# BroadNode.net
KiCad netlist of a schematic drawn in EasyEDA
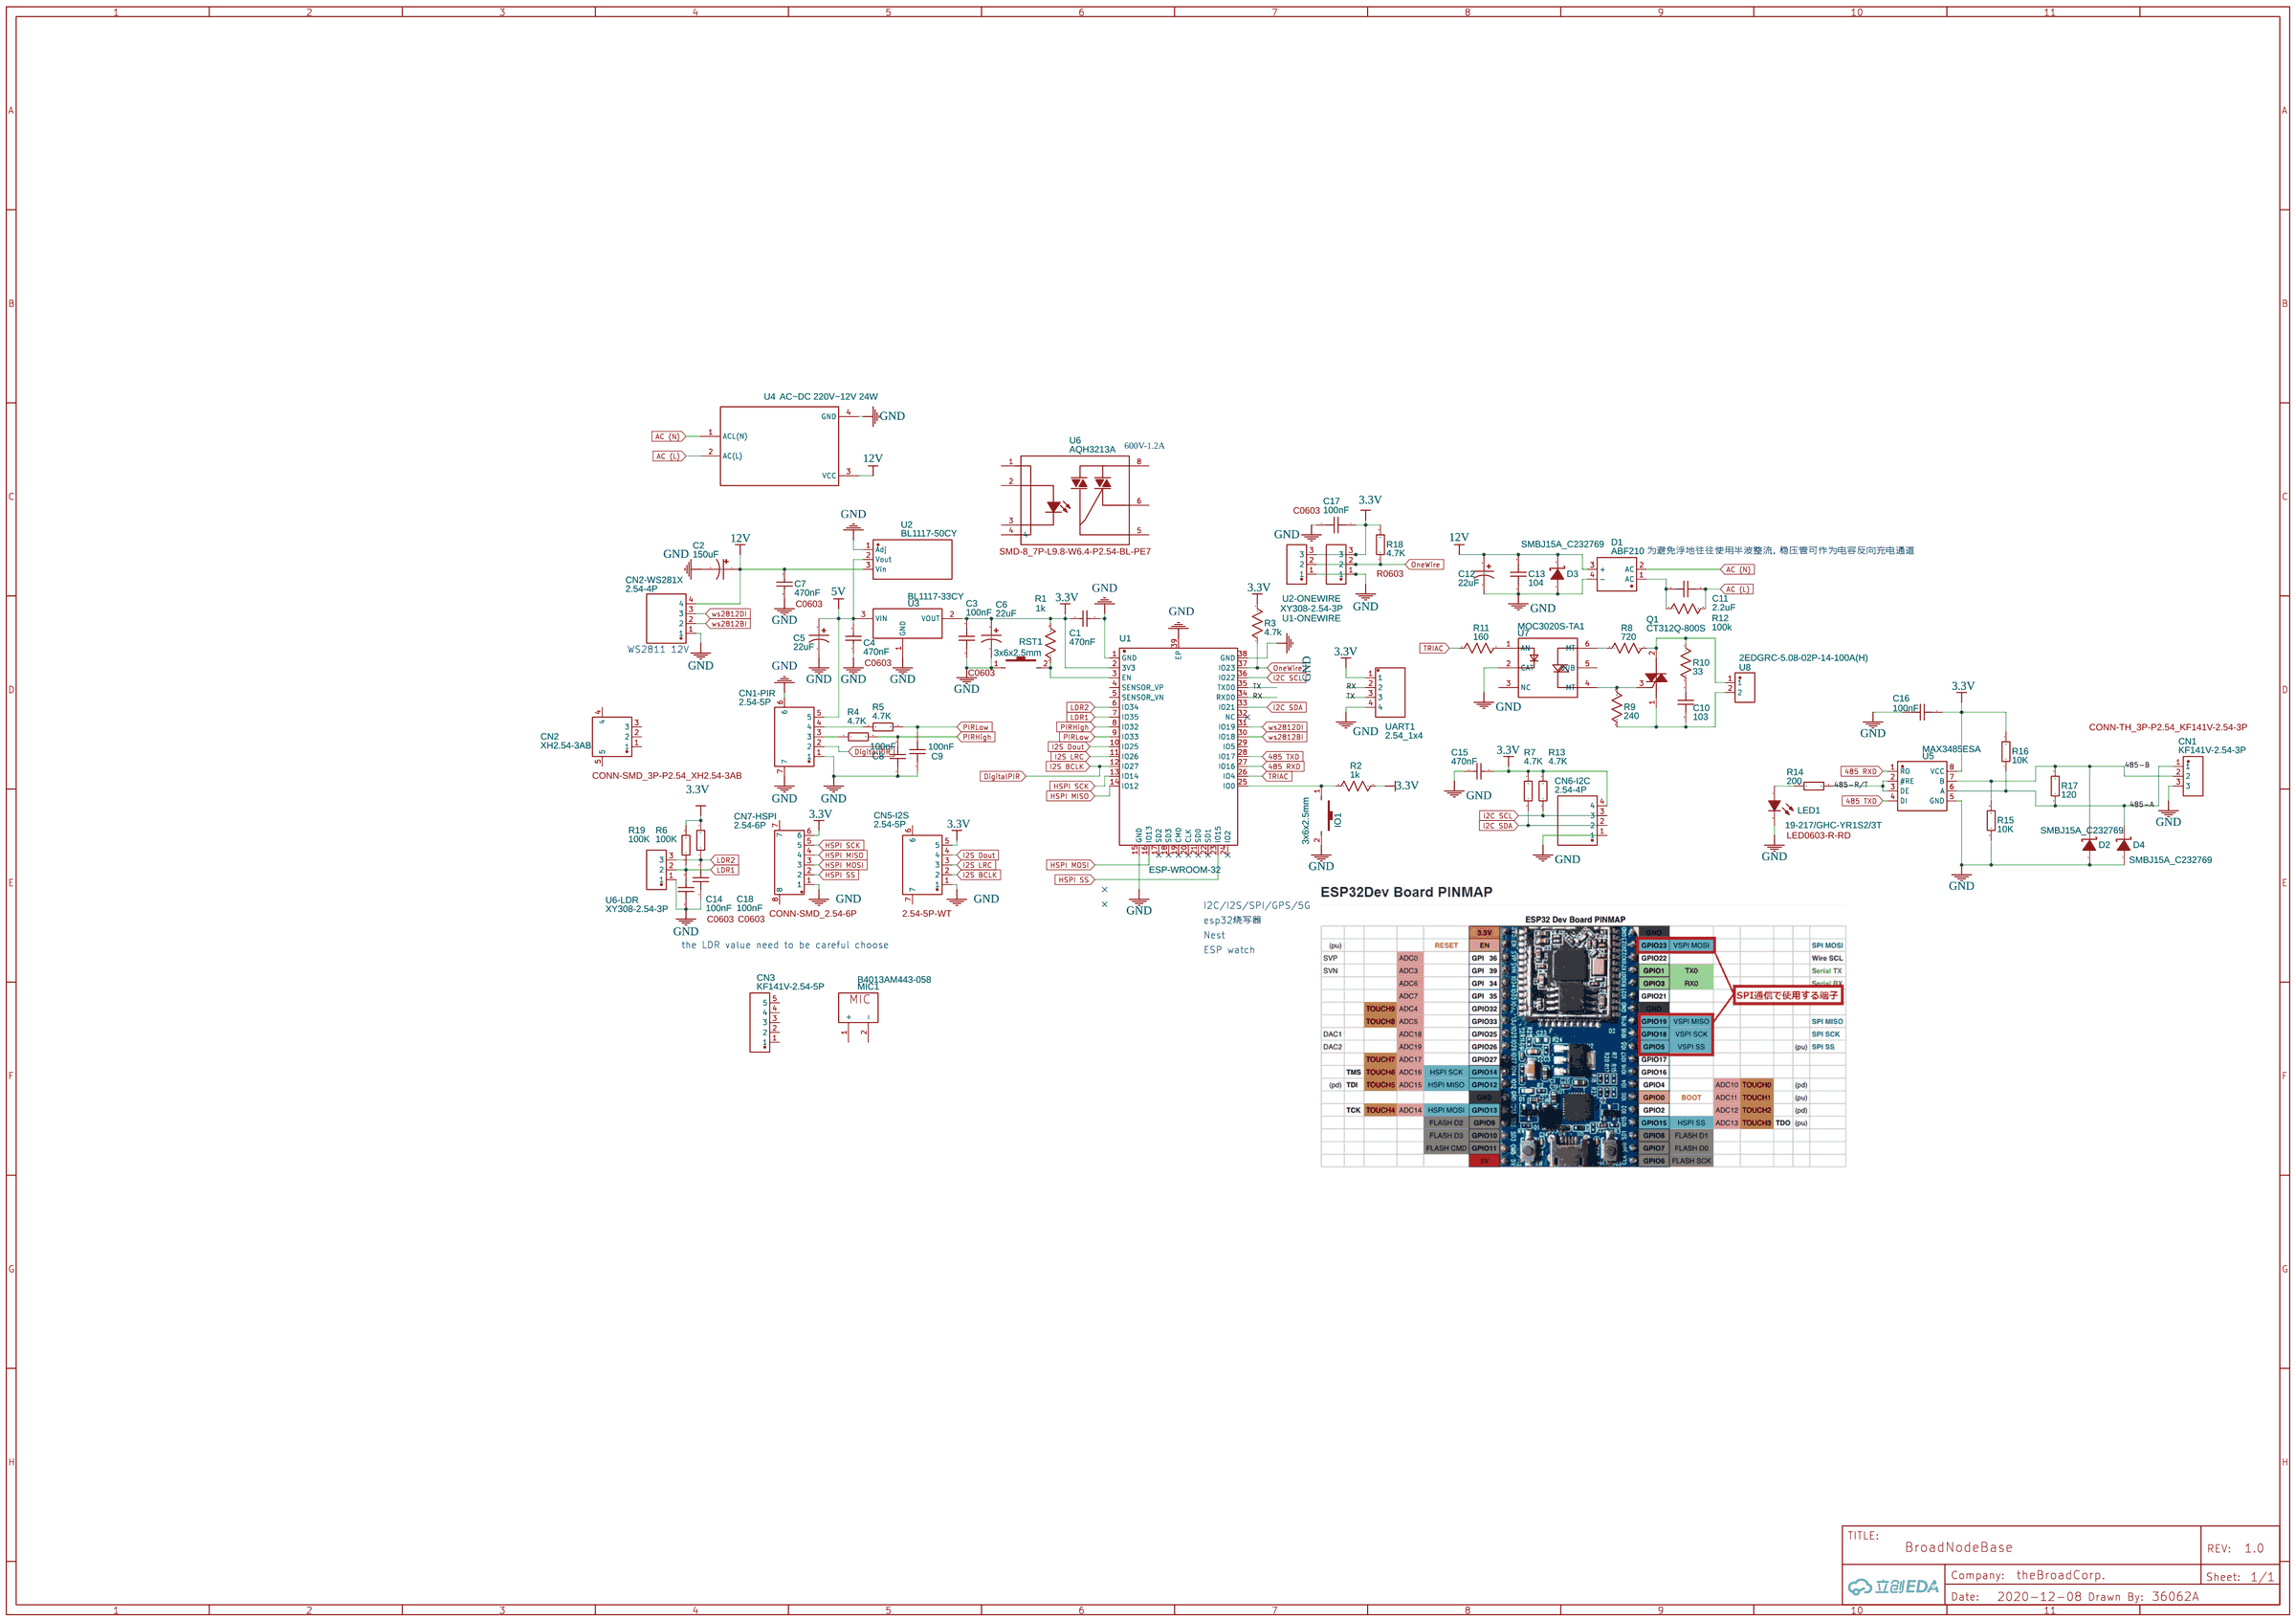
[diagram p0: schematic sheet]

(export (version "E")
  (design (tool "Eeschema 10.0.6"))
  (components
    (comp (ref "C1")
      (value "470nF")
      (fields
        (field (name "BOM_Manufacturer Part") "CL10B474KA8NNNC")
        (field (name "BOM_Supplier Part") "C1623")
      )
      (libsource (lib "") (part "CL10B474KA8NNNC"))
    )
    (comp (ref "C2")
      (value "150uF")
      (fields
        (field (name "BOM_Manufacturer Part") "OVZ151M1C0807-TRO")
        (field (name "BOM_Supplier Part") "C250092")
      )
      (libsource (lib "") (part "OVZ151M1C0807-TRO"))
    )
    (comp (ref "C3")
      (value "100nF")
      (fields
        (field (name "BOM_Manufacturer Part") "CC0603KRX7R9BB104")
        (field (name "BOM_Supplier Part") "C14663")
      )
      (libsource (lib "") (part "CC0603KRX7R9BB104_3"))
    )
    (comp (ref "C4")
      (value "470nF")
      (fields
        (field (name "BOM_Manufacturer Part") "CL10B474KA8NNNC")
        (field (name "BOM_Supplier Part") "C1623")
      )
      (libsource (lib "") (part "CL10B474KA8NNNC_2"))
    )
    (comp (ref "C5")
      (value "22uF")
      (fields
        (field (name "BOM_Manufacturer Part") "OCV220M1VTR-0606")
        (field (name "BOM_Supplier Part") "C473426")
      )
      (libsource (lib "") (part "OCV220M1VTR-0606"))
    )
    (comp (ref "C6")
      (value "22uF")
      (fields
        (field (name "BOM_Manufacturer Part") "OCV220M1VTR-0606")
        (field (name "BOM_Supplier Part") "C473426")
      )
      (libsource (lib "") (part "OCV220M1VTR-0606"))
    )
    (comp (ref "C7")
      (value "470nF")
      (fields
        (field (name "BOM_Manufacturer Part") "CL10B474KA8NNNC")
        (field (name "BOM_Supplier Part") "C1623")
      )
      (libsource (lib "") (part "CL10B474KA8NNNC_1"))
    )
    (comp (ref "C8")
      (value "100nF")
      (fields
        (field (name "BOM_Manufacturer Part") "CC0603KRX7R9BB104")
        (field (name "BOM_Supplier Part") "C14663")
      )
      (libsource (lib "") (part "CC0603KRX7R9BB104_1"))
    )
    (comp (ref "C9")
      (value "100nF")
      (fields
        (field (name "BOM_Manufacturer Part") "CC0603KRX7R9BB104")
        (field (name "BOM_Supplier Part") "C14663")
      )
      (libsource (lib "") (part "CC0603KRX7R9BB104_1"))
    )
    (comp (ref "C10") (value "103") (libsource (lib "") (part "Cap_0603_US_1")))
    (comp (ref "C11") (value "2.2uF") (libsource (lib "") (part "Cap_0603_US")))
    (comp (ref "C12")
      (value "22uF")
      (fields
        (field (name "BOM_Manufacturer Part") "OCV220M1VTR-0606")
        (field (name "BOM_Supplier Part") "C473426")
      )
      (libsource (lib "") (part "OCV220M1VTR-0606_1"))
    )
    (comp (ref "C13") (value "104") (libsource (lib "") (part "Cap_0603_US_1")))
    (comp (ref "C14")
      (value "100nF")
      (fields
        (field (name "BOM_Manufacturer Part") "CC0603KRX7R9BB104")
        (field (name "BOM_Supplier Part") "C14663")
      )
      (libsource (lib "") (part "CC0603KRX7R9BB104"))
    )
    (comp (ref "C15")
      (value "470nF")
      (fields
        (field (name "BOM_Manufacturer Part") "CL10B474KA8NNNC")
        (field (name "BOM_Supplier Part") "C1623")
      )
      (libsource (lib "") (part "CL10B474KA8NNNC"))
    )
    (comp (ref "C16")
      (value "100nF")
      (fields
        (field (name "BOM_Manufacturer Part") "CC0603KRX7R9BB104")
        (field (name "BOM_Supplier Part") "C14663")
      )
      (libsource (lib "") (part "CC0603KRX7R9BB104_4"))
    )
    (comp (ref "C17")
      (value "100nF")
      (fields
        (field (name "BOM_Manufacturer Part") "CC0603KRX7R9BB104")
        (field (name "BOM_Supplier Part") "C14663")
      )
      (libsource (lib "") (part "CC0603KRX7R9BB104_5"))
    )
    (comp (ref "C18")
      (value "100nF")
      (fields
        (field (name "BOM_Manufacturer Part") "CC0603KRX7R9BB104")
        (field (name "BOM_Supplier Part") "C14663")
      )
      (libsource (lib "") (part "CC0603KRX7R9BB104_2"))
    )
    (comp (ref "CN1")
      (value "KF141V-2.54-3P")
      (fields (field (name "BOM_Supplier Part") "C475115"))
      (libsource (lib "") (part "KF141V-2.54-3P"))
    )
    (comp (ref "CN1-PIR")
      (value "2.54-5P")
      (fields (field (name "BOM_Supplier Part") "C146121"))
      (libsource (lib "") (part "2.54-5P_1"))
    )
    (comp (ref "CN2")
      (value "XH2.54-3AB")
      (fields (field (name "BOM_Supplier Part") "C146126"))
      (libsource (lib "") (part "XH2.54-3AB"))
    )
    (comp (ref "CN2-WS281X")
      (value "2.54-4P")
      (fields (field (name "BOM_Supplier Part") "C146120"))
      (libsource (lib "") (part "2.54-4P_1"))
    )
    (comp (ref "CN3")
      (value "KF141V-2.54-5P")
      (fields (field (name "BOM_Supplier Part") "C475117"))
      (libsource (lib "") (part "KF141V-2.54-5P"))
    )
    (comp (ref "CN5-I2S")
      (value "2.54-5P")
      (fields (field (name "BOM_Supplier Part") "C146121"))
      (libsource (lib "") (part "2.54-5P"))
    )
    (comp (ref "CN6-I2C")
      (value "2.54-4P")
      (fields (field (name "BOM_Supplier Part") "C146120"))
      (libsource (lib "") (part "2.54-4P"))
    )
    (comp (ref "CN7-HSPI")
      (value "2.54-6P")
      (fields (field (name "BOM_Supplier Part") "C146122"))
      (libsource (lib "") (part "2.54-6P"))
    )
    (comp (ref "D1")
      (value "ABF210")
      (fields (field (name "BOM_Supplier Part") "C169534"))
      (libsource (lib "") (part "ABF210"))
    )
    (comp (ref "D2")
      (value "SMBJ15A_C232769")
      (fields (field (name "BOM_Manufacturer Part") "SMBJ15A") (field (name "BOM_Supplier Part") "C232769"))
      (libsource (lib "") (part "Unknown_2115_45"))
    )
    (comp (ref "D3")
      (value "SMBJ15A_C232769")
      (fields (field (name "BOM_Manufacturer Part") "SMBJ15A") (field (name "BOM_Supplier Part") "C232769"))
      (libsource (lib "") (part "Unknown_1575_-230"))
    )
    (comp (ref "D4")
      (value "SMBJ15A_C232769")
      (fields (field (name "BOM_Manufacturer Part") "SMBJ15A") (field (name "BOM_Supplier Part") "C232769"))
      (libsource (lib "") (part "Unknown_2150_45"))
    )
    (comp (ref "IO1")
      (value "3x6x2.5mm")
      (fields (field (name "BOM_Supplier Part") "C5382"))
      (libsource (lib "") (part "Unknown_1340_15"))
    )
    (comp (ref "LED1")
      (value "19-217/GHC-YR1S2/3T")
      (fields (field (name "BOM_Supplier Part") "C72043"))
      (libsource (lib "") (part "19-217/GHC-YR1S2/3T"))
    )
    (comp (ref "MIC1")
      (value "B4013AM443-058")
      (fields (field (name "BOM_Supplier Part") "C233795"))
      (libsource (lib "") (part "B4013AM443-058"))
    )
    (comp (ref "Q1")
      (value "CT312Q-800S")
      (fields (field (name "BOM_Supplier Part") "C527795"))
      (libsource (lib "") (part "CT312Q-800S"))
    )
    (comp (ref "R1") (value "1k") (libsource (lib "") (part "Res_0603(1/10W)_US")))
    (comp (ref "R2") (value "1k") (libsource (lib "") (part "Res_0603(1/10W)_US_1")))
    (comp (ref "R3") (value "4.7k") (libsource (lib "") (part "Res_0603(1/10W)_US")))
    (comp (ref "R4")
      (value "4.7K")
      (fields
        (field (name "BOM_Manufacturer Part") "0603WAF4701T5E")
        (field (name "BOM_Supplier Part") "C23162")
      )
      (libsource (lib "") (part "0603WAF4701T5E"))
    )
    (comp (ref "R5")
      (value "4.7K")
      (fields
        (field (name "BOM_Manufacturer Part") "0603WAF4701T5E")
        (field (name "BOM_Supplier Part") "C23162")
      )
      (libsource (lib "") (part "0603WAF4701T5E"))
    )
    (comp (ref "R6")
      (value "100K")
      (fields
        (field (name "BOM_Manufacturer Part") "0603WAF1003T5E")
        (field (name "BOM_Supplier Part") "C25803")
      )
      (libsource (lib "") (part "0603WAF1003T5E"))
    )
    (comp (ref "R7")
      (value "4.7K")
      (fields
        (field (name "BOM_Manufacturer Part") "0603WAF4701T5E")
        (field (name "BOM_Supplier Part") "C23162")
      )
      (libsource (lib "") (part "0603WAF4701T5E_2"))
    )
    (comp (ref "R8") (value "720") (libsource (lib "") (part "Res_0603(1/10W)_US_3")))
    (comp (ref "R9") (value "240") (libsource (lib "") (part "Res_0603(1/10W)_US")))
    (comp (ref "R10") (value "33") (libsource (lib "") (part "Res_0603(1/10W)_US_2")))
    (comp (ref "R11") (value "160") (libsource (lib "") (part "Res_0603(1/10W)_US_3")))
    (comp (ref "R12") (value "100k") (libsource (lib "") (part "Res_0603(1/10W)_US_1")))
    (comp (ref "R13")
      (value "4.7K")
      (fields
        (field (name "BOM_Manufacturer Part") "0603WAF4701T5E")
        (field (name "BOM_Supplier Part") "C23162")
      )
      (libsource (lib "") (part "0603WAF4701T5E_2"))
    )
    (comp (ref "R14")
      (value "200")
      (fields
        (field (name "BOM_Manufacturer Part") "MCR03EZPJ201")
        (field (name "BOM_Supplier Part") "C253407")
      )
      (libsource (lib "") (part "MCR03EZPJ201"))
    )
    (comp (ref "R15")
      (value "10K")
      (fields
        (field (name "BOM_Manufacturer Part") "RMCF0603JT10K0")
        (field (name "BOM_Supplier Part") "C238881")
      )
      (libsource (lib "") (part "RMCF0603JT10K0"))
    )
    (comp (ref "R16")
      (value "10K")
      (fields
        (field (name "BOM_Manufacturer Part") "RMCF0603JT10K0")
        (field (name "BOM_Supplier Part") "C238881")
      )
      (libsource (lib "") (part "RMCF0603JT10K0"))
    )
    (comp (ref "R17")
      (value "120")
      (fields
        (field (name "BOM_Manufacturer Part") "MCR03EZPFX1200")
        (field (name "BOM_Supplier Part") "C253379")
      )
      (libsource (lib "") (part "MCR03EZPFX1200"))
    )
    (comp (ref "R18")
      (value "4.7K")
      (fields
        (field (name "BOM_Manufacturer Part") "0603WAF4701T5E")
        (field (name "BOM_Supplier Part") "C23162")
      )
      (libsource (lib "") (part "0603WAF4701T5E_1"))
    )
    (comp (ref "R19")
      (value "100K")
      (fields
        (field (name "BOM_Manufacturer Part") "0603WAF1003T5E")
        (field (name "BOM_Supplier Part") "C25803")
      )
      (libsource (lib "") (part "0603WAF1003T5E"))
    )
    (comp (ref "RST1")
      (value "3x6x2.5mm")
      (fields (field (name "BOM_Supplier Part") "C5382"))
      (libsource (lib "") (part "Unknown_1030_-140"))
    )
    (comp (ref "U1")
      (value "ESP-WROOM-32")
      (fields (field (name "BOM_Supplier Part") "C95209"))
      (libsource (lib "") (part "Unknown_1190_-50"))
    )
    (comp (ref "U1-ONEWIRE")
      (value "XY308-2.54-3P")
      (fields (field (name "BOM_Supplier Part") "C557686"))
      (libsource (lib "") (part "XY308-2.54-3P_1"))
    )
    (comp (ref "U2")
      (value "BL1117-50CY")
      (fields (field (name "BOM_Supplier Part") "C194636"))
      (libsource (lib "") (part "BL1117-50CY"))
    )
    (comp (ref "U2-ONEWIRE")
      (value "XY308-2.54-3P")
      (fields (field (name "BOM_Supplier Part") "C557686"))
      (libsource (lib "") (part "XY308-2.54-3P_2"))
    )
    (comp (ref "U3")
      (value "BL1117-33CY")
      (fields (field (name "BOM_Supplier Part") "C165080"))
      (libsource (lib "") (part "BL1117-33CY"))
    )
    (comp (ref "U4")
      (value "AC~DC 220V~12V 24W")
      (fields (field (name "BOM_Manufacturer Part") "New SchematicLib"))
      (libsource (lib "") (part "AC&#126;DC 220V&#126;12V 24W"))
    )
    (comp (ref "U5")
      (value "MAX3485ESA")
      (fields (field (name "BOM_Supplier Part") "C668204"))
      (libsource (lib "") (part "MAX3485ESA"))
    )
    (comp (ref "U6")
      (value "AQH3213A")
      (fields (field (name "BOM_Supplier Part") "C91557"))
      (libsource (lib "") (part "AQH3213A"))
    )
    (comp (ref "U6-LDR")
      (value "XY308-2.54-3P")
      (fields (field (name "BOM_Supplier Part") "C557686"))
      (libsource (lib "") (part "XY308-2.54-3P"))
    )
    (comp (ref "U7")
      (value "MOC3020S-TA1")
      (fields (field (name "BOM_Supplier Part") "C115464"))
      (libsource (lib "") (part "MOC3020S-TA1"))
    )
    (comp (ref "U8")
      (value "2EDGRC-5.08-02P-14-100A(H)")
      (fields (field (name "BOM_Supplier Part") "C669314"))
      (libsource (lib "") (part "2EDGRC-5.08-02P-14-100A(H)"))
    )
    (comp (ref "UART1")
      (value "2.54_1x4")
      (fields
        (field (name "BOM_Manufacturer Part") "210S-1*4P L=11.6MMGold-plated black")
        (field (name "BOM_Supplier Part") "C124378")
      )
      (libsource (lib "") (part "Unknown_1400_-110"))
    )
  )
  (nets
    (net (code "1") (name "/485-A") (class "Default")
      (node (ref "CN1") (pin "1") (pinfunction "1_1") (pintype "unspecified"))
      (node (ref "D4") (pin "2") (pinfunction "K_2") (pintype "unspecified"))
      (node (ref "R16") (pin "1") (pinfunction "1_1") (pintype "unspecified"))
      (node (ref "R17") (pin "1") (pinfunction "1_1") (pintype "unspecified"))
      (node (ref "U5") (pin "6") (pinfunction "A_6") (pintype "unspecified"))
    )
    (net (code "2") (name "/485-B") (class "Default")
      (node (ref "CN1") (pin "2") (pinfunction "2_2") (pintype "unspecified"))
      (node (ref "D2") (pin "2") (pinfunction "K_2") (pintype "unspecified"))
      (node (ref "R15") (pin "2") (pinfunction "2_2") (pintype "unspecified"))
      (node (ref "R17") (pin "2") (pinfunction "2_2") (pintype "unspecified"))
      (node (ref "U5") (pin "7") (pinfunction "B_7") (pintype "unspecified"))
    )
    (net (code "3") (name "/485-R{slash}T") (class "Default")
      (node (ref "R14") (pin "2") (pinfunction "2_2") (pintype "unspecified"))
      (node (ref "U5") (pin "2") (pinfunction "#RE_2") (pintype "unspecified"))
      (node (ref "U5") (pin "3") (pinfunction "DE_3") (pintype "unspecified"))
    )
    (net (code "4") (name "/RX") (class "Default")
      (node (ref "U1") (pin "34") (pinfunction "RXD0_34") (pintype "unspecified"))
      (node (ref "UART1") (pin "2") (pinfunction "2_2") (pintype "unspecified"))
    )
    (net (code "5") (name "/TX") (class "Default")
      (node (ref "U1") (pin "35") (pinfunction "TXD0_35") (pintype "unspecified"))
      (node (ref "UART1") (pin "3") (pinfunction "3_3") (pintype "unspecified"))
    )
    (net (code "6") (name "3.3V") (class "Default")
      (node (ref "C1") (pin "2") (pinfunction "2_2") (pintype "input"))
      (node (ref "C15") (pin "1") (pinfunction "1_1") (pintype "input"))
      (node (ref "C16") (pin "1") (pinfunction "1_1") (pintype "unspecified"))
      (node (ref "C17") (pin "1") (pinfunction "1_1") (pintype "unspecified"))
      (node (ref "C3") (pin "2") (pinfunction "2_2") (pintype "unspecified"))
      (node (ref "C6") (pin "1") (pinfunction "1_1") (pintype "unspecified"))
      (node (ref "CN5-I2S") (pin "5") (pinfunction "5_5") (pintype "unspecified"))
      (node (ref "CN6-I2C") (pin "4") (pinfunction "4_4") (pintype "unspecified"))
      (node (ref "CN7-HSPI") (pin "6") (pinfunction "6_6") (pintype "unspecified"))
      (node (ref "R1") (pin "2") (pinfunction "2_2") (pintype "unspecified"))
      (node (ref "R13") (pin "2") (pinfunction "2_2") (pintype "input"))
      (node (ref "R16") (pin "2") (pinfunction "2_2") (pintype "unspecified"))
      (node (ref "R18") (pin "2") (pinfunction "2_2") (pintype "input"))
      (node (ref "R19") (pin "2") (pinfunction "2_2") (pintype "input"))
      (node (ref "R2") (pin "2") (pinfunction "2_2") (pintype "unspecified"))
      (node (ref "R3") (pin "2") (pinfunction "2_2") (pintype "unspecified"))
      (node (ref "R6") (pin "2") (pinfunction "2_2") (pintype "input"))
      (node (ref "R7") (pin "2") (pinfunction "2_2") (pintype "input"))
      (node (ref "U1") (pin "2") (pinfunction "3V3_2") (pintype "unspecified"))
      (node (ref "U1-ONEWIRE") (pin "3") (pinfunction "3_3") (pintype "unspecified"))
      (node (ref "U2-ONEWIRE") (pin "3") (pinfunction "3_3") (pintype "unspecified"))
      (node (ref "U3") (pin "2") (pinfunction "VOUT_2") (pintype "unspecified"))
      (node (ref "U5") (pin "8") (pinfunction "VCC_8") (pintype "unspecified"))
      (node (ref "UART1") (pin "1") (pinfunction "1_1") (pintype "unspecified"))
    )
    (net (code "7") (name "5V") (class "Default")
      (node (ref "C4") (pin "2") (pinfunction "2_2") (pintype "input"))
      (node (ref "C5") (pin "1") (pinfunction "1_1") (pintype "unspecified"))
      (node (ref "CN1-PIR") (pin "5") (pinfunction "5_5") (pintype "unspecified"))
      (node (ref "U2") (pin "2") (pinfunction "Vout_2") (pintype "unspecified"))
      (node (ref "U3") (pin "3") (pinfunction "VIN_3") (pintype "unspecified"))
    )
    (net (code "8") (name "12V") (class "Default")
      (node (ref "C12") (pin "1") (pinfunction "1_1") (pintype "unspecified"))
      (node (ref "C13") (pin "1") (pinfunction "1_1") (pintype "unspecified"))
      (node (ref "C2") (pin "1") (pinfunction "1_1") (pintype "unspecified"))
      (node (ref "C7") (pin "2") (pinfunction "2_2") (pintype "input"))
      (node (ref "CN2-WS281X") (pin "4") (pinfunction "4_4") (pintype "unspecified"))
      (node (ref "D1") (pin "3") (pinfunction "+_3") (pintype "unspecified"))
      (node (ref "D3") (pin "2") (pinfunction "K_2") (pintype "unspecified"))
      (node (ref "U2") (pin "3") (pinfunction "Vin_3") (pintype "unspecified"))
      (node (ref "U4") (pin "3") (pinfunction "VCC_3") (pintype "unspecified"))
    )
    (net (code "9") (name "485 RXD") (class "Default")
      (node (ref "U1") (pin "27") (pinfunction "IO16_27") (pintype "unspecified"))
      (node (ref "U5") (pin "1") (pinfunction "RO_1") (pintype "unspecified"))
    )
    (net (code "10") (name "485 TXD") (class "Default")
      (node (ref "U1") (pin "28") (pinfunction "IO17_28") (pintype "unspecified"))
      (node (ref "U5") (pin "4") (pinfunction "DI_4") (pintype "unspecified"))
    )
    (net (code "11") (name "AC (L)") (class "Default")
      (node (ref "C11") (pin "2") (pinfunction "2_2") (pintype "unspecified"))
      (node (ref "R12") (pin "2") (pinfunction "2_2") (pintype "unspecified"))
      (node (ref "U4") (pin "2") (pinfunction "AC(L)_2") (pintype "unspecified"))
    )
    (net (code "12") (name "AC (N)") (class "Default")
      (node (ref "D1") (pin "2") (pinfunction "AC_2") (pintype "unspecified"))
      (node (ref "U4") (pin "1") (pinfunction "ACL(N)_1") (pintype "unspecified"))
    )
    (net (code "13") (name "DigitalPIR") (class "Default")
      (node (ref "CN1-PIR") (pin "2") (pinfunction "2_2") (pintype "unspecified"))
      (node (ref "CN5-I2S") (pin "2") (pinfunction "2_2") (pintype "unspecified"))
      (node (ref "U1") (pin "12") (pinfunction "IO27_12") (pintype "unspecified"))
    )
    (net (code "14") (name "GND") (class "Default")
      (node (ref "C1") (pin "1") (pinfunction "1_1") (pintype "input"))
      (node (ref "C12") (pin "2") (pinfunction "2_2") (pintype "unspecified"))
      (node (ref "C13") (pin "2") (pinfunction "2_2") (pintype "unspecified"))
      (node (ref "C14") (pin "1") (pinfunction "1_1") (pintype "unspecified"))
      (node (ref "C15") (pin "2") (pinfunction "2_2") (pintype "input"))
      (node (ref "C16") (pin "2") (pinfunction "2_2") (pintype "unspecified"))
      (node (ref "C17") (pin "2") (pinfunction "2_2") (pintype "unspecified"))
      (node (ref "C18") (pin "1") (pinfunction "1_1") (pintype "unspecified"))
      (node (ref "C2") (pin "2") (pinfunction "2_2") (pintype "unspecified"))
      (node (ref "C3") (pin "1") (pinfunction "1_1") (pintype "unspecified"))
      (node (ref "C4") (pin "1") (pinfunction "1_1") (pintype "input"))
      (node (ref "C5") (pin "2") (pinfunction "2_2") (pintype "unspecified"))
      (node (ref "C6") (pin "2") (pinfunction "2_2") (pintype "unspecified"))
      (node (ref "C7") (pin "1") (pinfunction "1_1") (pintype "input"))
      (node (ref "C8") (pin "1") (pinfunction "1_1") (pintype "unspecified"))
      (node (ref "C9") (pin "1") (pinfunction "1_1") (pintype "unspecified"))
      (node (ref "CN1") (pin "3") (pinfunction "3_3") (pintype "unspecified"))
      (node (ref "CN1-PIR") (pin "1") (pinfunction "1_1") (pintype "unspecified"))
      (node (ref "CN1-PIR") (pin "6") (pinfunction "6_6") (pintype "unspecified"))
      (node (ref "CN1-PIR") (pin "7") (pinfunction "7_7") (pintype "unspecified"))
      (node (ref "CN2-WS281X") (pin "1") (pinfunction "1_1") (pintype "unspecified"))
      (node (ref "CN5-I2S") (pin "1") (pinfunction "1_1") (pintype "unspecified"))
      (node (ref "CN6-I2C") (pin "1") (pinfunction "1_1") (pintype "unspecified"))
      (node (ref "CN7-HSPI") (pin "1") (pinfunction "1_1") (pintype "unspecified"))
      (node (ref "D1") (pin "4") (pinfunction "-_4") (pintype "unspecified"))
      (node (ref "D2") (pin "1") (pinfunction "A_1") (pintype "unspecified"))
      (node (ref "D3") (pin "1") (pinfunction "A_1") (pintype "unspecified"))
      (node (ref "D4") (pin "1") (pinfunction "A_1") (pintype "unspecified"))
      (node (ref "IO1") (pin "2") (pinfunction "2_2") (pintype "input"))
      (node (ref "LED1") (pin "2") (pinfunction "C_2") (pintype "input"))
      (node (ref "R15") (pin "1") (pinfunction "1_1") (pintype "unspecified"))
      (node (ref "RST1") (pin "1") (pinfunction "1_1") (pintype "input"))
      (node (ref "U1") (pin "1") (pinfunction "GND_1") (pintype "unspecified"))
      (node (ref "U1") (pin "15") (pinfunction "GND_15") (pintype "unspecified"))
      (node (ref "U1") (pin "38") (pinfunction "GND_38") (pintype "unspecified"))
      (node (ref "U1") (pin "39") (pinfunction "EP_39") (pintype "unspecified"))
      (node (ref "U1-ONEWIRE") (pin "1") (pinfunction "1_1") (pintype "unspecified"))
      (node (ref "U2") (pin "1") (pinfunction "Adj_1") (pintype "unspecified"))
      (node (ref "U2-ONEWIRE") (pin "1") (pinfunction "1_1") (pintype "unspecified"))
      (node (ref "U3") (pin "1") (pinfunction "GND_1") (pintype "unspecified"))
      (node (ref "U4") (pin "4") (pinfunction "GND_4") (pintype "unspecified"))
      (node (ref "U5") (pin "5") (pinfunction "GND_5") (pintype "unspecified"))
      (node (ref "U6-LDR") (pin "1") (pinfunction "1_1") (pintype "unspecified"))
      (node (ref "U7") (pin "2") (pinfunction "CAT_2") (pintype "unspecified"))
      (node (ref "UART1") (pin "4") (pinfunction "4_4") (pintype "unspecified"))
    )
    (net (code "15") (name "HSPI MISO") (class "Default")
      (node (ref "CN7-HSPI") (pin "4") (pinfunction "4_4") (pintype "unspecified"))
      (node (ref "U1") (pin "14") (pinfunction "IO12_14") (pintype "unspecified"))
    )
    (net (code "16") (name "HSPI MOSI") (class "Default")
      (node (ref "CN7-HSPI") (pin "3") (pinfunction "3_3") (pintype "unspecified"))
      (node (ref "U1") (pin "16") (pinfunction "IO13_16") (pintype "unspecified"))
    )
    (net (code "17") (name "HSPI SCK") (class "Default")
      (node (ref "CN7-HSPI") (pin "5") (pinfunction "5_5") (pintype "unspecified"))
      (node (ref "U1") (pin "13") (pinfunction "IO14_13") (pintype "unspecified"))
    )
    (net (code "18") (name "HSPI SS") (class "Default")
      (node (ref "CN7-HSPI") (pin "2") (pinfunction "2_2") (pintype "unspecified"))
      (node (ref "U1") (pin "23") (pinfunction "IO15_23") (pintype "unspecified"))
    )
    (net (code "19") (name "I2C SCL") (class "Default")
      (node (ref "CN6-I2C") (pin "3") (pinfunction "3_3") (pintype "unspecified"))
      (node (ref "R13") (pin "1") (pinfunction "1_1") (pintype "input"))
      (node (ref "U1") (pin "36") (pinfunction "IO22_36") (pintype "unspecified"))
    )
    (net (code "20") (name "I2C SDA") (class "Default")
      (node (ref "CN6-I2C") (pin "2") (pinfunction "2_2") (pintype "unspecified"))
      (node (ref "R7") (pin "1") (pinfunction "1_1") (pintype "input"))
      (node (ref "U1") (pin "33") (pinfunction "IO21_33") (pintype "unspecified"))
    )
    (net (code "21") (name "I2S Dout") (class "Default")
      (node (ref "CN5-I2S") (pin "4") (pinfunction "4_4") (pintype "unspecified"))
      (node (ref "U1") (pin "10") (pinfunction "IO25_10") (pintype "unspecified"))
    )
    (net (code "22") (name "I2S LRC") (class "Default")
      (node (ref "CN5-I2S") (pin "3") (pinfunction "3_3") (pintype "unspecified"))
      (node (ref "U1") (pin "11") (pinfunction "IO26_11") (pintype "unspecified"))
    )
    (net (code "23") (name "LDR1") (class "Default")
      (node (ref "C14") (pin "2") (pinfunction "2_2") (pintype "unspecified"))
      (node (ref "R19") (pin "1") (pinfunction "1_1") (pintype "input"))
      (node (ref "U1") (pin "7") (pinfunction "IO35_7") (pintype "unspecified"))
      (node (ref "U6-LDR") (pin "2") (pinfunction "2_2") (pintype "unspecified"))
    )
    (net (code "24") (name "LDR2") (class "Default")
      (node (ref "C18") (pin "2") (pinfunction "2_2") (pintype "unspecified"))
      (node (ref "R6") (pin "1") (pinfunction "1_1") (pintype "input"))
      (node (ref "U1") (pin "6") (pinfunction "IO34_6") (pintype "unspecified"))
      (node (ref "U6-LDR") (pin "3") (pinfunction "3_3") (pintype "unspecified"))
    )
    (net (code "25") (name "Net-(C10-Pad1)") (class "Default")
      (node (ref "C10") (pin "1") (pinfunction "1_1") (pintype "unspecified"))
      (node (ref "R10") (pin "2") (pinfunction "2_2") (pintype "unspecified"))
    )
    (net (code "26") (name "Net-(C11-Pad1)") (class "Default")
      (node (ref "C11") (pin "1") (pinfunction "1_1") (pintype "unspecified"))
      (node (ref "D1") (pin "1") (pinfunction "AC_1") (pintype "unspecified"))
      (node (ref "R12") (pin "1") (pinfunction "1_1") (pintype "unspecified"))
    )
    (net (code "27") (name "Net-(CN1-PIR-Pad3)") (class "Default")
      (node (ref "CN1-PIR") (pin "3") (pinfunction "3_3") (pintype "unspecified"))
      (node (ref "R4") (pin "1") (pinfunction "1_1") (pintype "input"))
    )
    (net (code "28") (name "Net-(CN1-PIR-Pad4)") (class "Default")
      (node (ref "CN1-PIR") (pin "4") (pinfunction "4_4") (pintype "unspecified"))
      (node (ref "R5") (pin "1") (pinfunction "1_1") (pintype "input"))
    )
    (net (code "29") (name "Net-(LED1-A)") (class "Default")
      (node (ref "LED1") (pin "1") (pinfunction "A_1") (pintype "input"))
      (node (ref "R14") (pin "1") (pinfunction "1_1") (pintype "unspecified"))
    )
    (net (code "30") (name "Net-(Q1-G)") (class "Default")
      (node (ref "Q1") (pin "3") (pinfunction "G_3") (pintype "unspecified"))
      (node (ref "R9") (pin "2") (pinfunction "2_2") (pintype "unspecified"))
      (node (ref "U7") (pin "4") (pinfunction "MT_4") (pintype "unspecified"))
    )
    (net (code "31") (name "Net-(Q1-T1)") (class "Default")
      (node (ref "C10") (pin "2") (pinfunction "2_2") (pintype "unspecified"))
      (node (ref "Q1") (pin "1") (pinfunction "T1_1") (pintype "unspecified"))
      (node (ref "R9") (pin "1") (pinfunction "1_1") (pintype "unspecified"))
      (node (ref "U8") (pin "2") (pinfunction "2_2") (pintype "unspecified"))
    )
    (net (code "32") (name "Net-(Q1-T2)") (class "Default")
      (node (ref "Q1") (pin "2") (pinfunction "T2_2") (pintype "unspecified"))
      (node (ref "R10") (pin "1") (pinfunction "1_1") (pintype "unspecified"))
      (node (ref "R8") (pin "1") (pinfunction "1_1") (pintype "unspecified"))
      (node (ref "U8") (pin "1") (pinfunction "1_1") (pintype "unspecified"))
    )
    (net (code "33") (name "Net-(R8-Pad2)") (class "Default")
      (node (ref "R8") (pin "2") (pinfunction "2_2") (pintype "unspecified"))
      (node (ref "U7") (pin "6") (pinfunction "MT_6") (pintype "unspecified"))
    )
    (net (code "34") (name "Net-(U1-EN)") (class "Default")
      (node (ref "R1") (pin "1") (pinfunction "1_1") (pintype "unspecified"))
      (node (ref "RST1") (pin "2") (pinfunction "2_2") (pintype "input"))
      (node (ref "U1") (pin "3") (pinfunction "EN_3") (pintype "unspecified"))
    )
    (net (code "35") (name "Net-(U1-IO0)") (class "Default")
      (node (ref "IO1") (pin "1") (pinfunction "1_1") (pintype "input"))
      (node (ref "R2") (pin "1") (pinfunction "1_1") (pintype "unspecified"))
      (node (ref "U1") (pin "25") (pinfunction "IO0_25") (pintype "unspecified"))
    )
    (net (code "36") (name "Net-(U7-AN)") (class "Default")
      (node (ref "R11") (pin "1") (pinfunction "1_1") (pintype "unspecified"))
      (node (ref "U7") (pin "1") (pinfunction "AN_1") (pintype "unspecified"))
    )
    (net (code "37") (name "OneWire") (class "Default")
      (node (ref "R18") (pin "1") (pinfunction "1_1") (pintype "input"))
      (node (ref "R3") (pin "1") (pinfunction "1_1") (pintype "unspecified"))
      (node (ref "U1") (pin "37") (pinfunction "IO23_37") (pintype "unspecified"))
      (node (ref "U1-ONEWIRE") (pin "2") (pinfunction "2_2") (pintype "unspecified"))
      (node (ref "U2-ONEWIRE") (pin "2") (pinfunction "2_2") (pintype "unspecified"))
    )
    (net (code "38") (name "PIRHigh") (class "Default")
      (node (ref "C8") (pin "2") (pinfunction "2_2") (pintype "unspecified"))
      (node (ref "R4") (pin "2") (pinfunction "2_2") (pintype "input"))
      (node (ref "U1") (pin "8") (pinfunction "IO32_8") (pintype "unspecified"))
    )
    (net (code "39") (name "PIRLow") (class "Default")
      (node (ref "C9") (pin "2") (pinfunction "2_2") (pintype "unspecified"))
      (node (ref "R5") (pin "2") (pinfunction "2_2") (pintype "input"))
      (node (ref "U1") (pin "9") (pinfunction "IO33_9") (pintype "unspecified"))
    )
    (net (code "40") (name "TRIAC") (class "Default")
      (node (ref "R11") (pin "2") (pinfunction "2_2") (pintype "unspecified"))
      (node (ref "U1") (pin "26") (pinfunction "IO4_26") (pintype "unspecified"))
    )
    (net (code "41") (name "unconnected-(CN2-Pad1)") (class "Default")
      (node (ref "CN2") (pin "1") (pinfunction "1_1") (pintype "unspecified"))
    )
    (net (code "42") (name "unconnected-(CN2-Pad2)") (class "Default")
      (node (ref "CN2") (pin "2") (pinfunction "2_2") (pintype "unspecified"))
    )
    (net (code "43") (name "unconnected-(CN2-Pad3)") (class "Default")
      (node (ref "CN2") (pin "3") (pinfunction "3_3") (pintype "unspecified"))
    )
    (net (code "44") (name "unconnected-(CN2-Pad4)") (class "Default")
      (node (ref "CN2") (pin "4") (pinfunction "4_4") (pintype "unspecified"))
    )
    (net (code "45") (name "unconnected-(CN2-Pad5)") (class "Default")
      (node (ref "CN2") (pin "5") (pinfunction "5_5") (pintype "unspecified"))
    )
    (net (code "46") (name "unconnected-(CN3-Pad1)") (class "Default")
      (node (ref "CN3") (pin "1") (pinfunction "1_1") (pintype "unspecified"))
    )
    (net (code "47") (name "unconnected-(CN3-Pad2)") (class "Default")
      (node (ref "CN3") (pin "2") (pinfunction "2_2") (pintype "unspecified"))
    )
    (net (code "48") (name "unconnected-(CN3-Pad3)") (class "Default")
      (node (ref "CN3") (pin "3") (pinfunction "3_3") (pintype "unspecified"))
    )
    (net (code "49") (name "unconnected-(CN3-Pad4)") (class "Default")
      (node (ref "CN3") (pin "4") (pinfunction "4_4") (pintype "unspecified"))
    )
    (net (code "50") (name "unconnected-(CN3-Pad5)") (class "Default")
      (node (ref "CN3") (pin "5") (pinfunction "5_5") (pintype "unspecified"))
    )
    (net (code "51") (name "unconnected-(CN5-I2S-Pad6)") (class "Default")
      (node (ref "CN5-I2S") (pin "6") (pinfunction "6_6") (pintype "unspecified"))
    )
    (net (code "52") (name "unconnected-(CN5-I2S-Pad7)") (class "Default")
      (node (ref "CN5-I2S") (pin "7") (pinfunction "7_7") (pintype "unspecified"))
    )
    (net (code "53") (name "unconnected-(CN7-HSPI-Pad7)") (class "Default")
      (node (ref "CN7-HSPI") (pin "7") (pinfunction "7_7") (pintype "unspecified"))
    )
    (net (code "54") (name "unconnected-(CN7-HSPI-Pad8)") (class "Default")
      (node (ref "CN7-HSPI") (pin "8") (pinfunction "8_8") (pintype "unspecified"))
    )
    (net (code "55") (name "unconnected-(MIC1-+-Pad1)") (class "Default")
      (node (ref "MIC1") (pin "1") (pinfunction "+_1") (pintype "unspecified"))
    )
    (net (code "56") (name "unconnected-(MIC1---Pad2)") (class "Default")
      (node (ref "MIC1") (pin "2") (pinfunction "-_2") (pintype "unspecified"))
    )
    (net (code "57") (name "unconnected-(U1-CLK-Pad20)") (class "Default")
      (node (ref "U1") (pin "20") (pinfunction "CLK_20") (pintype "unspecified+no_connect"))
    )
    (net (code "58") (name "unconnected-(U1-CMD-Pad19)") (class "Default")
      (node (ref "U1") (pin "19") (pinfunction "CMD_19") (pintype "unspecified+no_connect"))
    )
    (net (code "59") (name "unconnected-(U1-IO2-Pad24)") (class "Default")
      (node (ref "U1") (pin "24") (pinfunction "IO2_24") (pintype "unspecified+no_connect"))
    )
    (net (code "60") (name "unconnected-(U1-IO5-Pad29)") (class "Default")
      (node (ref "U1") (pin "29") (pinfunction "IO5_29") (pintype "unspecified"))
    )
    (net (code "61") (name "unconnected-(U1-NC-Pad32)") (class "Default")
      (node (ref "U1") (pin "32") (pinfunction "NC_32") (pintype "unspecified+no_connect"))
    )
    (net (code "62") (name "unconnected-(U1-SD0-Pad21)") (class "Default")
      (node (ref "U1") (pin "21") (pinfunction "SD0_21") (pintype "unspecified+no_connect"))
    )
    (net (code "63") (name "unconnected-(U1-SD1-Pad22)") (class "Default")
      (node (ref "U1") (pin "22") (pinfunction "SD1_22") (pintype "unspecified+no_connect"))
    )
    (net (code "64") (name "unconnected-(U1-SD2-Pad17)") (class "Default")
      (node (ref "U1") (pin "17") (pinfunction "SD2_17") (pintype "unspecified+no_connect"))
    )
    (net (code "65") (name "unconnected-(U1-SD3-Pad18)") (class "Default")
      (node (ref "U1") (pin "18") (pinfunction "SD3_18") (pintype "unspecified+no_connect"))
    )
    (net (code "66") (name "unconnected-(U1-SENSOR_VN-Pad5)") (class "Default")
      (node (ref "U1") (pin "5") (pinfunction "SENSOR_VN_5") (pintype "unspecified"))
    )
    (net (code "67") (name "unconnected-(U1-SENSOR_VP-Pad4)") (class "Default")
      (node (ref "U1") (pin "4") (pinfunction "SENSOR_VP_4") (pintype "unspecified"))
    )
    (net (code "68") (name "unconnected-(U6-Pad1)") (class "Default")
      (node (ref "U6") (pin "1") (pinfunction "1_1") (pintype "unspecified"))
    )
    (net (code "69") (name "unconnected-(U6-Pad2)") (class "Default")
      (node (ref "U6") (pin "2") (pinfunction "2_2") (pintype "unspecified"))
    )
    (net (code "70") (name "unconnected-(U6-Pad3)") (class "Default")
      (node (ref "U6") (pin "3") (pinfunction "3_3") (pintype "unspecified"))
    )
    (net (code "71") (name "unconnected-(U6-Pad4)") (class "Default")
      (node (ref "U6") (pin "4") (pinfunction "4_4") (pintype "unspecified"))
    )
    (net (code "72") (name "unconnected-(U6-Pad5)") (class "Default")
      (node (ref "U6") (pin "5") (pinfunction "5_5") (pintype "unspecified"))
    )
    (net (code "73") (name "unconnected-(U6-Pad6)") (class "Default")
      (node (ref "U6") (pin "6") (pinfunction "6_6") (pintype "unspecified"))
    )
    (net (code "74") (name "unconnected-(U6-Pad8)") (class "Default")
      (node (ref "U6") (pin "8") (pinfunction "8_8") (pintype "unspecified"))
    )
    (net (code "75") (name "unconnected-(U7-NC-Pad3)") (class "Default")
      (node (ref "U7") (pin "3") (pinfunction "NC_3") (pintype "unspecified"))
    )
    (net (code "76") (name "unconnected-(U7-SUB-Pad5)") (class "Default")
      (node (ref "U7") (pin "5") (pinfunction "SUB_5") (pintype "unspecified"))
    )
    (net (code "77") (name "ws2812BI") (class "Default")
      (node (ref "CN2-WS281X") (pin "2") (pinfunction "2_2") (pintype "unspecified"))
      (node (ref "U1") (pin "30") (pinfunction "IO18_30") (pintype "unspecified"))
    )
    (net (code "78") (name "ws2812DI") (class "Default")
      (node (ref "CN2-WS281X") (pin "3") (pinfunction "3_3") (pintype "unspecified"))
      (node (ref "U1") (pin "31") (pinfunction "IO19_31") (pintype "unspecified"))
    )
  )
)
